# power_supply_board.net
KiCad netlist of a schematic drawn in EAGLE
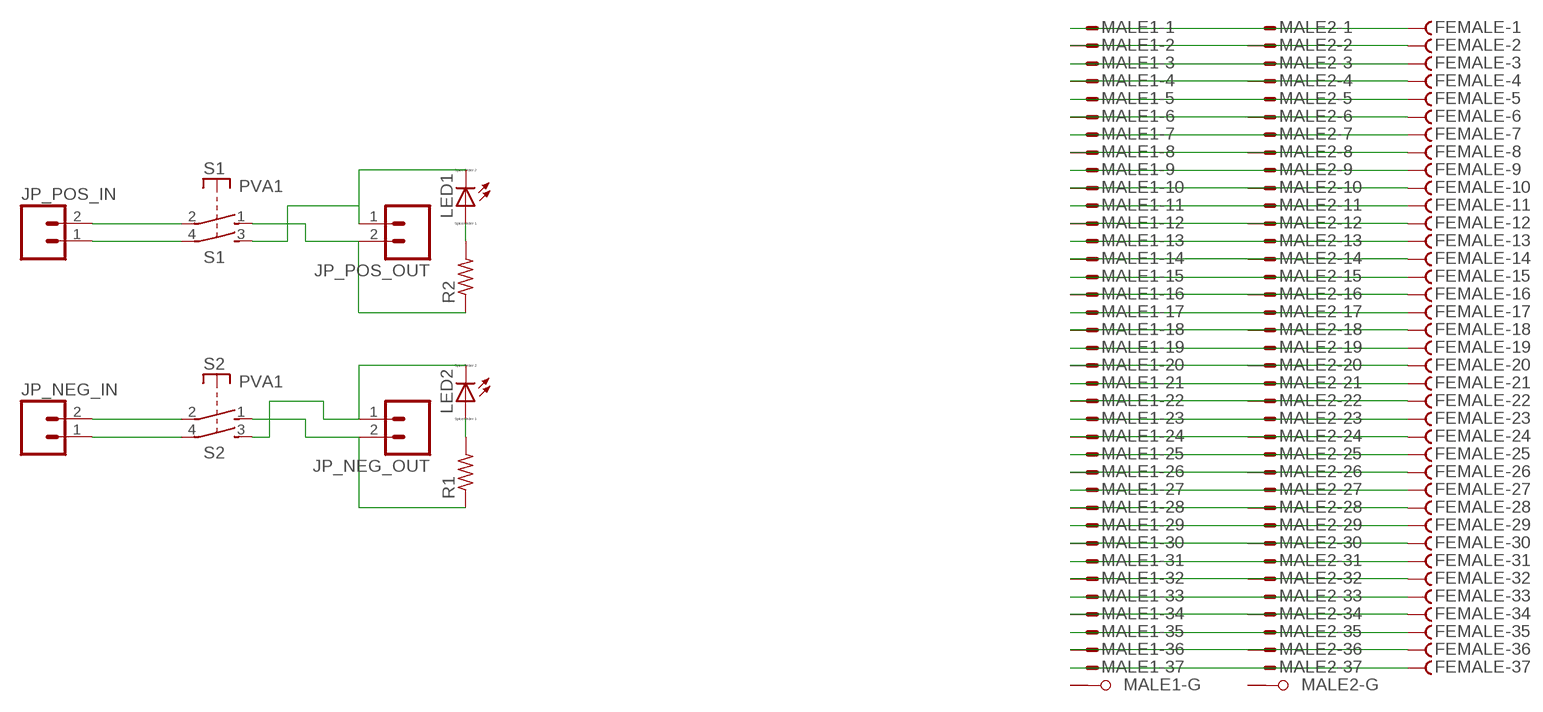
[diagram p0: schematic, sheet 1]

(export (version "E")
  (design (tool "Eeschema 10.0.6"))
  (components
    (comp (ref "FEMALE")
      (value "F37HPS")
      (footprint "eagle-import:F37HP")
      (libsource (lib "eagle-import") (part "F37?SHP"))
    )
    (comp (ref "JP_NEG_IN")
      (value "M02-JST-2MM-SMT")
      (footprint "eagle-import:JST-2-SMD")
      (libsource (lib "eagle-import") (part "M02-JST-2MM-SMT"))
    )
    (comp (ref "JP_NEG_OUT")
      (value "M02-JST-2MM-SMT")
      (footprint "eagle-import:JST-2-SMD")
      (libsource (lib "eagle-import") (part "M02-JST-2MM-SMT"))
    )
    (comp (ref "JP_POS_IN")
      (value "M02-JST-2MM-SMT")
      (footprint "eagle-import:JST-2-SMD")
      (libsource (lib "eagle-import") (part "M02-JST-2MM-SMT"))
    )
    (comp (ref "JP_POS_OUT")
      (value "M02-JST-2MM-SMT")
      (footprint "eagle-import:JST-2-SMD")
      (libsource (lib "eagle-import") (part "M02-JST-2MM-SMT"))
    )
    (comp (ref "LED1")
      (value "LED_ELED0402")
      (footprint "eagle-import:C0402")
      (libsource (lib "eagle-import") (part "LED_ELED0402"))
    )
    (comp (ref "LED2")
      (value "LED_ELED0402")
      (footprint "eagle-import:C0402")
      (libsource (lib "eagle-import") (part "LED_ELED0402"))
    )
    (comp (ref "MALE1")
      (value "M37HPS")
      (footprint "eagle-import:M37HP")
      (libsource (lib "eagle-import") (part "M37HPS"))
    )
    (comp (ref "MALE2")
      (value "M37HPS")
      (footprint "eagle-import:M37HP")
      (libsource (lib "eagle-import") (part "M37HPS"))
    )
    (comp (ref "R1")
      (value "R-US_R0805")
      (footprint "eagle-import:R0805")
      (libsource (lib "eagle-import") (part "R-US_R0805"))
    )
    (comp (ref "R2")
      (value "R-US_R0805")
      (footprint "eagle-import:R0805")
      (libsource (lib "eagle-import") (part "R-US_R0805"))
    )
    (comp (ref "S1")
      (value "PVA1")
      (footprint "eagle-import:PVA1F")
      (libsource (lib "eagle-import") (part "PVA1"))
    )
    (comp (ref "S2")
      (value "PVA1")
      (footprint "eagle-import:PVA1F")
      (libsource (lib "eagle-import") (part "PVA1"))
    )
  )
  (nets
    (net (code "1") (name "Net-(FEMALEA-F)") (class "Default")
      (node (ref "FEMALE") (pin "1") (pinfunction "F_1") (pintype "passive"))
      (node (ref "MALE1") (pin "1") (pinfunction "M_1") (pintype "passive"))
      (node (ref "MALE2") (pin "1") (pinfunction "M_1") (pintype "passive"))
    )
    (net (code "2") (name "Net-(FEMALEAA-F)") (class "Default")
      (node (ref "FEMALE") (pin "33") (pinfunction "F_33") (pintype "passive"))
      (node (ref "MALE1") (pin "33") (pinfunction "M_33") (pintype "passive"))
      (node (ref "MALE2") (pin "33") (pinfunction "M_33") (pintype "passive"))
    )
    (net (code "3") (name "Net-(FEMALEAB-F)") (class "Default")
      (node (ref "FEMALE") (pin "34") (pinfunction "F_34") (pintype "passive"))
      (node (ref "MALE1") (pin "34") (pinfunction "M_34") (pintype "passive"))
      (node (ref "MALE2") (pin "34") (pinfunction "M_34") (pintype "passive"))
    )
    (net (code "4") (name "Net-(FEMALEAC-F)") (class "Default")
      (node (ref "FEMALE") (pin "35") (pinfunction "F_35") (pintype "passive"))
      (node (ref "MALE1") (pin "35") (pinfunction "M_35") (pintype "passive"))
      (node (ref "MALE2") (pin "35") (pinfunction "M_35") (pintype "passive"))
    )
    (net (code "5") (name "Net-(FEMALEAD-F)") (class "Default")
      (node (ref "FEMALE") (pin "36") (pinfunction "F_36") (pintype "passive"))
      (node (ref "MALE1") (pin "36") (pinfunction "M_36") (pintype "passive"))
      (node (ref "MALE2") (pin "36") (pinfunction "M_36") (pintype "passive"))
    )
    (net (code "6") (name "Net-(FEMALEAE-F)") (class "Default")
      (node (ref "FEMALE") (pin "37") (pinfunction "F_37") (pintype "passive"))
      (node (ref "MALE1") (pin "37") (pinfunction "M_37") (pintype "passive"))
      (node (ref "MALE2") (pin "37") (pinfunction "M_37") (pintype "passive"))
    )
    (net (code "7") (name "Net-(FEMALEAF-F)") (class "Default")
      (node (ref "FEMALE") (pin "4") (pinfunction "F_4") (pintype "passive"))
      (node (ref "MALE1") (pin "4") (pinfunction "M_4") (pintype "passive"))
      (node (ref "MALE2") (pin "4") (pinfunction "M_4") (pintype "passive"))
    )
    (net (code "8") (name "Net-(FEMALEAG-F)") (class "Default")
      (node (ref "FEMALE") (pin "5") (pinfunction "F_5") (pintype "passive"))
      (node (ref "MALE1") (pin "5") (pinfunction "M_5") (pintype "passive"))
      (node (ref "MALE2") (pin "5") (pinfunction "M_5") (pintype "passive"))
    )
    (net (code "9") (name "Net-(FEMALEAH-F)") (class "Default")
      (node (ref "FEMALE") (pin "6") (pinfunction "F_6") (pintype "passive"))
      (node (ref "MALE1") (pin "6") (pinfunction "M_6") (pintype "passive"))
      (node (ref "MALE2") (pin "6") (pinfunction "M_6") (pintype "passive"))
    )
    (net (code "10") (name "Net-(FEMALEAI-F)") (class "Default")
      (node (ref "FEMALE") (pin "7") (pinfunction "F_7") (pintype "passive"))
      (node (ref "MALE1") (pin "7") (pinfunction "M_7") (pintype "passive"))
      (node (ref "MALE2") (pin "7") (pinfunction "M_7") (pintype "passive"))
    )
    (net (code "11") (name "Net-(FEMALEAJ-F)") (class "Default")
      (node (ref "FEMALE") (pin "8") (pinfunction "F_8") (pintype "passive"))
      (node (ref "MALE1") (pin "8") (pinfunction "M_8") (pintype "passive"))
      (node (ref "MALE2") (pin "8") (pinfunction "M_8") (pintype "passive"))
    )
    (net (code "12") (name "Net-(FEMALEAK-F)") (class "Default")
      (node (ref "FEMALE") (pin "9") (pinfunction "F_9") (pintype "passive"))
      (node (ref "MALE1") (pin "9") (pinfunction "M_9") (pintype "passive"))
      (node (ref "MALE2") (pin "9") (pinfunction "M_9") (pintype "passive"))
    )
    (net (code "13") (name "Net-(FEMALEB-F)") (class "Default")
      (node (ref "FEMALE") (pin "10") (pinfunction "F_10") (pintype "passive"))
      (node (ref "MALE1") (pin "10") (pinfunction "M_10") (pintype "passive"))
      (node (ref "MALE2") (pin "10") (pinfunction "M_10") (pintype "passive"))
    )
    (net (code "14") (name "Net-(FEMALEC-F)") (class "Default")
      (node (ref "FEMALE") (pin "11") (pinfunction "F_11") (pintype "passive"))
      (node (ref "MALE1") (pin "11") (pinfunction "M_11") (pintype "passive"))
      (node (ref "MALE2") (pin "11") (pinfunction "M_11") (pintype "passive"))
    )
    (net (code "15") (name "Net-(FEMALED-F)") (class "Default")
      (node (ref "FEMALE") (pin "12") (pinfunction "F_12") (pintype "passive"))
      (node (ref "MALE1") (pin "12") (pinfunction "M_12") (pintype "passive"))
      (node (ref "MALE2") (pin "12") (pinfunction "M_12") (pintype "passive"))
    )
    (net (code "16") (name "Net-(FEMALEE-F)") (class "Default")
      (node (ref "FEMALE") (pin "13") (pinfunction "F_13") (pintype "passive"))
      (node (ref "MALE1") (pin "13") (pinfunction "M_13") (pintype "passive"))
      (node (ref "MALE2") (pin "13") (pinfunction "M_13") (pintype "passive"))
    )
    (net (code "17") (name "Net-(FEMALEF-F)") (class "Default")
      (node (ref "FEMALE") (pin "14") (pinfunction "F_14") (pintype "passive"))
      (node (ref "MALE1") (pin "14") (pinfunction "M_14") (pintype "passive"))
      (node (ref "MALE2") (pin "14") (pinfunction "M_14") (pintype "passive"))
    )
    (net (code "18") (name "Net-(FEMALEG-F)") (class "Default")
      (node (ref "FEMALE") (pin "15") (pinfunction "F_15") (pintype "passive"))
      (node (ref "MALE1") (pin "15") (pinfunction "M_15") (pintype "passive"))
      (node (ref "MALE2") (pin "15") (pinfunction "M_15") (pintype "passive"))
    )
    (net (code "19") (name "Net-(FEMALEH-F)") (class "Default")
      (node (ref "FEMALE") (pin "16") (pinfunction "F_16") (pintype "passive"))
      (node (ref "MALE1") (pin "16") (pinfunction "M_16") (pintype "passive"))
      (node (ref "MALE2") (pin "16") (pinfunction "M_16") (pintype "passive"))
    )
    (net (code "20") (name "Net-(FEMALEI-F)") (class "Default")
      (node (ref "FEMALE") (pin "17") (pinfunction "F_17") (pintype "passive"))
      (node (ref "MALE1") (pin "17") (pinfunction "M_17") (pintype "passive"))
      (node (ref "MALE2") (pin "17") (pinfunction "M_17") (pintype "passive"))
    )
    (net (code "21") (name "Net-(FEMALEJ-F)") (class "Default")
      (node (ref "FEMALE") (pin "18") (pinfunction "F_18") (pintype "passive"))
      (node (ref "MALE1") (pin "18") (pinfunction "M_18") (pintype "passive"))
      (node (ref "MALE2") (pin "18") (pinfunction "M_18") (pintype "passive"))
    )
    (net (code "22") (name "Net-(FEMALEK-F)") (class "Default")
      (node (ref "FEMALE") (pin "19") (pinfunction "F_19") (pintype "passive"))
      (node (ref "MALE1") (pin "19") (pinfunction "M_19") (pintype "passive"))
      (node (ref "MALE2") (pin "19") (pinfunction "M_19") (pintype "passive"))
    )
    (net (code "23") (name "Net-(FEMALEL-F)") (class "Default")
      (node (ref "FEMALE") (pin "2") (pinfunction "F_2") (pintype "passive"))
      (node (ref "MALE1") (pin "2") (pinfunction "M_2") (pintype "passive"))
      (node (ref "MALE2") (pin "2") (pinfunction "M_2") (pintype "passive"))
    )
    (net (code "24") (name "Net-(FEMALEM-F)") (class "Default")
      (node (ref "FEMALE") (pin "20") (pinfunction "F_20") (pintype "passive"))
      (node (ref "MALE1") (pin "20") (pinfunction "M_20") (pintype "passive"))
      (node (ref "MALE2") (pin "20") (pinfunction "M_20") (pintype "passive"))
    )
    (net (code "25") (name "Net-(FEMALEN-F)") (class "Default")
      (node (ref "FEMALE") (pin "21") (pinfunction "F_21") (pintype "passive"))
      (node (ref "MALE1") (pin "21") (pinfunction "M_21") (pintype "passive"))
      (node (ref "MALE2") (pin "21") (pinfunction "M_21") (pintype "passive"))
    )
    (net (code "26") (name "Net-(FEMALEO-F)") (class "Default")
      (node (ref "FEMALE") (pin "22") (pinfunction "F_22") (pintype "passive"))
      (node (ref "MALE1") (pin "22") (pinfunction "M_22") (pintype "passive"))
      (node (ref "MALE2") (pin "22") (pinfunction "M_22") (pintype "passive"))
    )
    (net (code "27") (name "Net-(FEMALEP-F)") (class "Default")
      (node (ref "FEMALE") (pin "23") (pinfunction "F_23") (pintype "passive"))
      (node (ref "MALE1") (pin "23") (pinfunction "M_23") (pintype "passive"))
      (node (ref "MALE2") (pin "23") (pinfunction "M_23") (pintype "passive"))
    )
    (net (code "28") (name "Net-(FEMALEQ-F)") (class "Default")
      (node (ref "FEMALE") (pin "24") (pinfunction "F_24") (pintype "passive"))
      (node (ref "MALE1") (pin "24") (pinfunction "M_24") (pintype "passive"))
      (node (ref "MALE2") (pin "24") (pinfunction "M_24") (pintype "passive"))
    )
    (net (code "29") (name "Net-(FEMALER-F)") (class "Default")
      (node (ref "FEMALE") (pin "25") (pinfunction "F_25") (pintype "passive"))
      (node (ref "MALE1") (pin "25") (pinfunction "M_25") (pintype "passive"))
      (node (ref "MALE2") (pin "25") (pinfunction "M_25") (pintype "passive"))
    )
    (net (code "30") (name "Net-(FEMALES-F)") (class "Default")
      (node (ref "FEMALE") (pin "26") (pinfunction "F_26") (pintype "passive"))
      (node (ref "MALE1") (pin "26") (pinfunction "M_26") (pintype "passive"))
      (node (ref "MALE2") (pin "26") (pinfunction "M_26") (pintype "passive"))
    )
    (net (code "31") (name "Net-(FEMALET-F)") (class "Default")
      (node (ref "FEMALE") (pin "27") (pinfunction "F_27") (pintype "passive"))
      (node (ref "MALE1") (pin "27") (pinfunction "M_27") (pintype "passive"))
      (node (ref "MALE2") (pin "27") (pinfunction "M_27") (pintype "passive"))
    )
    (net (code "32") (name "Net-(FEMALEU-F)") (class "Default")
      (node (ref "FEMALE") (pin "28") (pinfunction "F_28") (pintype "passive"))
      (node (ref "MALE1") (pin "28") (pinfunction "M_28") (pintype "passive"))
      (node (ref "MALE2") (pin "28") (pinfunction "M_28") (pintype "passive"))
    )
    (net (code "33") (name "Net-(FEMALEV-F)") (class "Default")
      (node (ref "FEMALE") (pin "29") (pinfunction "F_29") (pintype "passive"))
      (node (ref "MALE1") (pin "29") (pinfunction "M_29") (pintype "passive"))
      (node (ref "MALE2") (pin "29") (pinfunction "M_29") (pintype "passive"))
    )
    (net (code "34") (name "Net-(FEMALEW-F)") (class "Default")
      (node (ref "FEMALE") (pin "3") (pinfunction "F_3") (pintype "passive"))
      (node (ref "MALE1") (pin "3") (pinfunction "M_3") (pintype "passive"))
      (node (ref "MALE2") (pin "3") (pinfunction "M_3") (pintype "passive"))
    )
    (net (code "35") (name "Net-(FEMALEX-F)") (class "Default")
      (node (ref "FEMALE") (pin "30") (pinfunction "F_30") (pintype "passive"))
      (node (ref "MALE1") (pin "30") (pinfunction "M_30") (pintype "passive"))
      (node (ref "MALE2") (pin "30") (pinfunction "M_30") (pintype "passive"))
    )
    (net (code "36") (name "Net-(FEMALEY-F)") (class "Default")
      (node (ref "FEMALE") (pin "31") (pinfunction "F_31") (pintype "passive"))
      (node (ref "MALE1") (pin "31") (pinfunction "M_31") (pintype "passive"))
      (node (ref "MALE2") (pin "31") (pinfunction "M_31") (pintype "passive"))
    )
    (net (code "37") (name "Net-(FEMALEZ-F)") (class "Default")
      (node (ref "FEMALE") (pin "32") (pinfunction "F_32") (pintype "passive"))
      (node (ref "MALE1") (pin "32") (pinfunction "M_32") (pintype "passive"))
      (node (ref "MALE2") (pin "32") (pinfunction "M_32") (pintype "passive"))
    )
    (net (code "38") (name "Net-(LED1-PadA)") (class "Default")
      (node (ref "LED1") (pin "A") (pinfunction "A_A") (pintype "passive"))
      (node (ref "R2") (pin "2") (pinfunction "2_2") (pintype "passive"))
    )
    (net (code "39") (name "Net-(LED2-PadA)") (class "Default")
      (node (ref "LED2") (pin "A") (pinfunction "A_A") (pintype "passive"))
      (node (ref "R1") (pin "2") (pinfunction "2_2") (pintype "passive"))
    )
    (net (code "40") (name "Net-(S1A-P)") (class "Default")
      (node (ref "JP_POS_IN") (pin "2") (pinfunction "2_2") (pintype "passive"))
      (node (ref "S1") (pin "2") (pinfunction "P_2") (pintype "passive"))
    )
    (net (code "41") (name "Net-(S1A-S)") (class "Default")
      (node (ref "JP_POS_OUT") (pin "2") (pinfunction "2_2") (pintype "passive"))
      (node (ref "R2") (pin "1") (pinfunction "1_1") (pintype "passive"))
      (node (ref "S1") (pin "1") (pinfunction "S_1") (pintype "passive"))
    )
    (net (code "42") (name "Net-(S1B-P)") (class "Default")
      (node (ref "JP_POS_IN") (pin "1") (pinfunction "1_1") (pintype "passive"))
      (node (ref "S1") (pin "4") (pinfunction "P_4") (pintype "passive"))
    )
    (net (code "43") (name "Net-(S1B-S)") (class "Default")
      (node (ref "JP_POS_OUT") (pin "1") (pinfunction "1_1") (pintype "passive"))
      (node (ref "LED1") (pin "C") (pinfunction "C_C") (pintype "passive"))
      (node (ref "S1") (pin "3") (pinfunction "S_3") (pintype "passive"))
    )
    (net (code "44") (name "Net-(S2A-P)") (class "Default")
      (node (ref "JP_NEG_IN") (pin "2") (pinfunction "2_2") (pintype "passive"))
      (node (ref "S2") (pin "2") (pinfunction "P_2") (pintype "passive"))
    )
    (net (code "45") (name "Net-(S2A-S)") (class "Default")
      (node (ref "JP_NEG_OUT") (pin "2") (pinfunction "2_2") (pintype "passive"))
      (node (ref "R1") (pin "1") (pinfunction "1_1") (pintype "passive"))
      (node (ref "S2") (pin "1") (pinfunction "S_1") (pintype "passive"))
    )
    (net (code "46") (name "Net-(S2B-P)") (class "Default")
      (node (ref "JP_NEG_IN") (pin "1") (pinfunction "1_1") (pintype "passive"))
      (node (ref "S2") (pin "4") (pinfunction "P_4") (pintype "passive"))
    )
    (net (code "47") (name "Net-(S2B-S)") (class "Default")
      (node (ref "JP_NEG_OUT") (pin "1") (pinfunction "1_1") (pintype "passive"))
      (node (ref "LED2") (pin "C") (pinfunction "C_C") (pintype "passive"))
      (node (ref "S2") (pin "3") (pinfunction "S_3") (pintype "passive"))
    )
    (net (code "48") (name "unconnected-(MALE1-PadG1)") (class "Default")
      (node (ref "MALE1") (pin "G1") (pinfunction "G1_G1") (pintype "passive"))
    )
    (net (code "49") (name "unconnected-(MALE1-PadG2)") (class "Default")
      (node (ref "MALE1") (pin "G2") (pinfunction "G2_G2") (pintype "passive"))
    )
    (net (code "50") (name "unconnected-(MALE2-PadG1)") (class "Default")
      (node (ref "MALE2") (pin "G1") (pinfunction "G1_G1") (pintype "passive"))
    )
    (net (code "51") (name "unconnected-(MALE2-PadG2)") (class "Default")
      (node (ref "MALE2") (pin "G2") (pinfunction "G2_G2") (pintype "passive"))
    )
  )
)
